# PPU2_And_Connector.net
KiCad netlist of a schematic drawn in Altium Designer
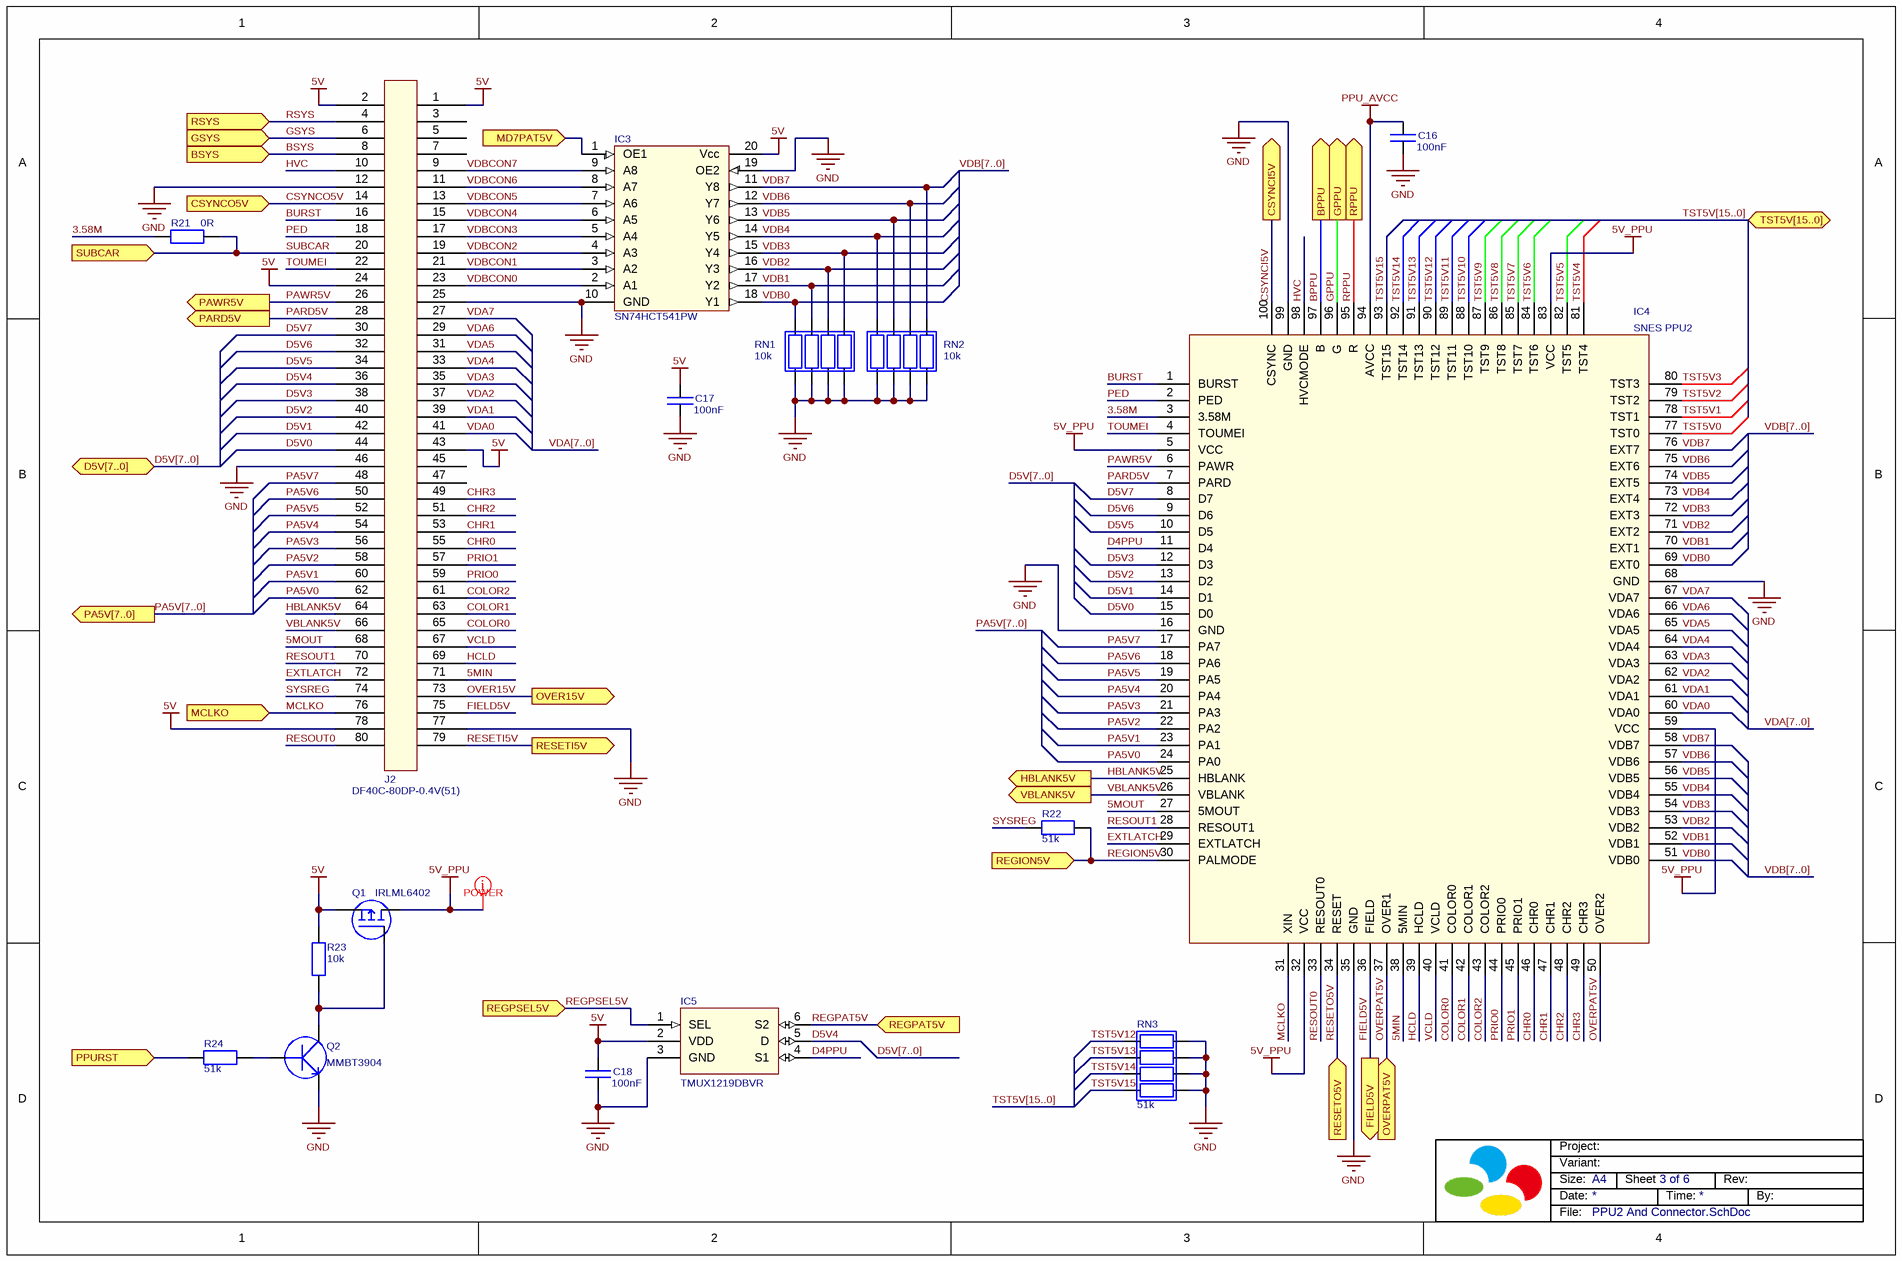
[diagram p0: PPU2 And Connector.SchDoc]

(export (version "E")
  (design (tool "Eeschema 10.0.6"))
  (components
    (comp (ref "C16")
      (value "100nF")
      (footprint "Cap_0402_Chip")
      (fields
        (field (name "TOLERANCE") "±20%")
        (field (name "Comment") "Ceramic Capacitor 100nF 10V ±20% X7R 0402")
      )
      (libsource (lib "PCB") (part "Capacitor"))
    )
    (comp (ref "C17")
      (value "100nF")
      (footprint "Cap_0402_Chip")
      (fields
        (field (name "TOLERANCE") "±20%")
        (field (name "Comment") "Ceramic Capacitor 100nF 10V ±20% X7R 0402")
      )
      (libsource (lib "PCB") (part "Capacitor"))
    )
    (comp (ref "C18")
      (value "100nF")
      (footprint "Cap_0402_Chip")
      (fields
        (field (name "TOLERANCE") "±20%")
        (field (name "Comment") "Ceramic Capacitor 100nF 10V ±20% X7R 0402")
      )
      (libsource (lib "PCB") (part "Capacitor"))
    )
    (comp (ref "IC3")
      (value "SN74HCT541")
      (footprint "TSSOP20 Narrow")
      (fields (field (name "MANUFACTURER_PART_NUMBER") "SN74HCT541PW"))
      (libsource (lib "PCB") (part "SN74HCT541"))
    )
    (comp (ref "IC4")
      (value "SNES PPU2")
      (footprint "PPU100Pin")
      (description "PPU2")
      (libsource (lib "PCB") (part "PPU2100Pin"))
    )
    (comp (ref "IC5")
      (value "TMUX1219")
      (footprint "SOT23-6")
      (description "2:1 MUX")
      (fields (field (name "MANUFACTURER_PART_NUMBER") "TMUX1219DBVR"))
      (libsource (lib "PCB") (part "TMUX1219"))
    )
    (comp (ref "J2")
      (value "DF40C-80DP")
      (footprint "DF40C-80DP")
      (description "80Pole Connector")
      (fields (field (name "MANUFACTURER_PART_NUMBER") "DF40C-80DP-0.4V(51)"))
      (libsource (lib "PCB") (part "Conn 80P"))
    )
    (comp (ref "Q1") (value "IRLML6402") (footprint "SOT23_FET") (libsource (lib "PCB") (part "Mosfet1")))
    (comp (ref "Q2") (value "MMBT3904") (footprint "SOT23_Transistor") (libsource (lib "PCB") (part "T_NPN")))
    (comp (ref "R21")
      (value "0R")
      (footprint "Res_0603_Chip")
      (fields (field (name "TOLERANCE") "±1%") (field (name "Comment") "Resistor 0R 0603 ±1%"))
      (libsource (lib "") (part "R_2"))
    )
    (comp (ref "R22")
      (value "51k")
      (footprint "Res_0402_Chip")
      (fields (field (name "TOLERANCE") "±1%") (field (name "Comment") "Resistor 51k 0402 ±1%"))
      (libsource (lib "") (part "R_2"))
    )
    (comp (ref "R23")
      (value "10k")
      (footprint "Res_0402_Chip")
      (fields (field (name "TOLERANCE") "±1%") (field (name "Comment") "Resistor 10k 0402 ±1%"))
      (libsource (lib "") (part "R_1"))
    )
    (comp (ref "R24")
      (value "51k")
      (footprint "Res_0402_Chip")
      (fields (field (name "TOLERANCE") "±1%") (field (name "Comment") "Resistor 51k 0402 ±1%"))
      (libsource (lib "PCB") (part "R"))
    )
    (comp (ref "RN1")
      (value "10k")
      (footprint "1206_Array_Chip")
      (fields (field (name "TOLERANCE") "±1%") (field (name "Comment") "Resistor Network 10k 1206 ±1%"))
      (libsource (lib "") (part "RNetwork_1"))
    )
    (comp (ref "RN2")
      (value "10k")
      (footprint "1206_Array_Chip")
      (fields (field (name "TOLERANCE") "±1%") (field (name "Comment") "Resistor Network 10k 1206 ±1%"))
      (libsource (lib "") (part "RNetwork_1"))
    )
    (comp (ref "RN3")
      (value "51k")
      (footprint "1206_Array_Chip")
      (fields (field (name "TOLERANCE") "±1%") (field (name "Comment") "Resistor Network 51k 1206 ±1%"))
      (libsource (lib "PCB") (part "RNetwork"))
    )
  )
  (nets
    (net (code "1") (name "/3.58M") (class "Default")
      (node (ref "IC4") (pin "3") (pinfunction "3.58M_3") (pintype "passive"))
      (node (ref "R21") (pin "2") (pintype "passive"))
    )
    (net (code "2") (name "/5MIN") (class "Default")
      (node (ref "IC4") (pin "38") (pinfunction "5MIN_38") (pintype "passive"))
      (node (ref "J2") (pin "71") (pintype "passive"))
    )
    (net (code "3") (name "/5MOUT") (class "Default")
      (node (ref "IC4") (pin "27") (pinfunction "5MOUT_27") (pintype "passive"))
      (node (ref "J2") (pin "68") (pintype "passive"))
    )
    (net (code "4") (name "/BPPU") (class "Default")
      (node (ref "IC4") (pin "97") (pinfunction "B_97") (pintype "passive"))
    )
    (net (code "5") (name "/BSYS") (class "Default") (node (ref "J2") (pin "8") (pintype "passive")))
    (net (code "6") (name "/BURST") (class "Default")
      (node (ref "IC4") (pin "1") (pinfunction "BURST_1") (pintype "passive"))
      (node (ref "J2") (pin "16") (pintype "passive"))
    )
    (net (code "7") (name "/CHR0") (class "Default")
      (node (ref "IC4") (pin "46") (pinfunction "CHR0_46") (pintype "passive"))
      (node (ref "J2") (pin "55") (pintype "passive"))
    )
    (net (code "8") (name "/CHR1") (class "Default")
      (node (ref "IC4") (pin "47") (pinfunction "CHR1_47") (pintype "passive"))
      (node (ref "J2") (pin "53") (pintype "passive"))
    )
    (net (code "9") (name "/CHR2") (class "Default")
      (node (ref "IC4") (pin "48") (pinfunction "CHR2_48") (pintype "passive"))
      (node (ref "J2") (pin "51") (pintype "passive"))
    )
    (net (code "10") (name "/CHR3") (class "Default")
      (node (ref "IC4") (pin "49") (pinfunction "CHR3_49") (pintype "passive"))
      (node (ref "J2") (pin "49") (pintype "passive"))
    )
    (net (code "11") (name "/COLOR0") (class "Default")
      (node (ref "IC4") (pin "41") (pinfunction "COLOR0_41") (pintype "passive"))
      (node (ref "J2") (pin "65") (pintype "passive"))
    )
    (net (code "12") (name "/COLOR1") (class "Default")
      (node (ref "IC4") (pin "42") (pinfunction "COLOR1_42") (pintype "passive"))
      (node (ref "J2") (pin "63") (pintype "passive"))
    )
    (net (code "13") (name "/COLOR2") (class "Default")
      (node (ref "IC4") (pin "43") (pinfunction "COLOR2_43") (pintype "passive"))
      (node (ref "J2") (pin "61") (pintype "passive"))
    )
    (net (code "14") (name "/CSYNCI5V") (class "Default")
      (node (ref "IC4") (pin "100") (pinfunction "CSYNC_100") (pintype "passive"))
    )
    (net (code "15") (name "/CSYNCO5V") (class "Default") (node (ref "J2") (pin "14") (pintype "passive")))
    (net (code "16") (name "/D4PPU") (class "Default")
      (node (ref "IC4") (pin "11") (pinfunction "D4_11") (pintype "passive"))
      (node (ref "IC5") (pin "4") (pinfunction "S1_4") (pintype "bidirectional"))
    )
    (net (code "17") (name "/D5V0") (class "Default")
      (node (ref "IC4") (pin "15") (pinfunction "D0_15") (pintype "passive"))
      (node (ref "J2") (pin "44") (pintype "passive"))
    )
    (net (code "18") (name "/D5V1") (class "Default")
      (node (ref "IC4") (pin "14") (pinfunction "D1_14") (pintype "passive"))
      (node (ref "J2") (pin "42") (pintype "passive"))
    )
    (net (code "19") (name "/D5V2") (class "Default")
      (node (ref "IC4") (pin "13") (pinfunction "D2_13") (pintype "passive"))
      (node (ref "J2") (pin "40") (pintype "passive"))
    )
    (net (code "20") (name "/D5V3") (class "Default")
      (node (ref "IC4") (pin "12") (pinfunction "D3_12") (pintype "passive"))
      (node (ref "J2") (pin "38") (pintype "passive"))
    )
    (net (code "21") (name "/D5V4") (class "Default")
      (node (ref "IC5") (pin "5") (pinfunction "D_5") (pintype "bidirectional"))
      (node (ref "J2") (pin "36") (pintype "passive"))
    )
    (net (code "22") (name "/D5V5") (class "Default")
      (node (ref "IC4") (pin "10") (pinfunction "D5_10") (pintype "passive"))
      (node (ref "J2") (pin "34") (pintype "passive"))
    )
    (net (code "23") (name "/D5V6") (class "Default")
      (node (ref "IC4") (pin "9") (pinfunction "D6_9") (pintype "passive"))
      (node (ref "J2") (pin "32") (pintype "passive"))
    )
    (net (code "24") (name "/D5V7") (class "Default")
      (node (ref "IC4") (pin "8") (pinfunction "D7_8") (pintype "passive"))
      (node (ref "J2") (pin "30") (pintype "passive"))
    )
    (net (code "26") (name "/EXTLATCH") (class "Default")
      (node (ref "IC4") (pin "29") (pinfunction "EXTLATCH_29") (pintype "passive"))
      (node (ref "J2") (pin "72") (pintype "passive"))
    )
    (net (code "27") (name "/FIELD5V") (class "Default")
      (node (ref "IC4") (pin "36") (pinfunction "FIELD_36") (pintype "passive"))
      (node (ref "J2") (pin "75") (pintype "passive"))
    )
    (net (code "28") (name "/GPPU") (class "Default")
      (node (ref "IC4") (pin "96") (pinfunction "G_96") (pintype "passive"))
    )
    (net (code "29") (name "/GSYS") (class "Default") (node (ref "J2") (pin "6") (pintype "passive")))
    (net (code "30") (name "/HBLANK5V") (class "Default")
      (node (ref "IC4") (pin "25") (pinfunction "HBLANK_25") (pintype "passive"))
      (node (ref "J2") (pin "64") (pintype "passive"))
    )
    (net (code "31") (name "/HCLD") (class "Default")
      (node (ref "IC4") (pin "39") (pinfunction "HCLD_39") (pintype "passive"))
      (node (ref "J2") (pin "69") (pintype "passive"))
    )
    (net (code "32") (name "/HVC") (class "Default")
      (node (ref "IC4") (pin "98") (pinfunction "HVCMODE_98") (pintype "passive"))
      (node (ref "J2") (pin "10") (pintype "passive"))
    )
    (net (code "33") (name "/MCLKO") (class "Default")
      (node (ref "IC4") (pin "31") (pinfunction "XIN_31") (pintype "passive"))
      (node (ref "J2") (pin "76") (pintype "passive"))
    )
    (net (code "34") (name "/MD7PAT5V") (class "Default")
      (node (ref "IC3") (pin "1") (pinfunction "OE1_1") (pintype "input"))
    )
    (net (code "35") (name "/OVER15V") (class "Default") (node (ref "J2") (pin "73") (pintype "passive")))
    (net (code "36") (name "/OVERPAT5V") (class "Default")
      (node (ref "IC4") (pin "37") (pinfunction "OVER1_37") (pintype "passive"))
      (node (ref "IC4") (pin "50") (pinfunction "OVER2_50") (pintype "passive"))
    )
    (net (code "37") (name "/PA5V0") (class "Default")
      (node (ref "IC4") (pin "24") (pinfunction "PA0_24") (pintype "passive"))
      (node (ref "J2") (pin "62") (pintype "passive"))
    )
    (net (code "38") (name "/PA5V1") (class "Default")
      (node (ref "IC4") (pin "23") (pinfunction "PA1_23") (pintype "passive"))
      (node (ref "J2") (pin "60") (pintype "passive"))
    )
    (net (code "39") (name "/PA5V2") (class "Default")
      (node (ref "IC4") (pin "22") (pinfunction "PA2_22") (pintype "passive"))
      (node (ref "J2") (pin "58") (pintype "passive"))
    )
    (net (code "40") (name "/PA5V3") (class "Default")
      (node (ref "IC4") (pin "21") (pinfunction "PA3_21") (pintype "passive"))
      (node (ref "J2") (pin "56") (pintype "passive"))
    )
    (net (code "41") (name "/PA5V4") (class "Default")
      (node (ref "IC4") (pin "20") (pinfunction "PA4_20") (pintype "passive"))
      (node (ref "J2") (pin "54") (pintype "passive"))
    )
    (net (code "42") (name "/PA5V5") (class "Default")
      (node (ref "IC4") (pin "19") (pinfunction "PA5_19") (pintype "passive"))
      (node (ref "J2") (pin "52") (pintype "passive"))
    )
    (net (code "43") (name "/PA5V6") (class "Default")
      (node (ref "IC4") (pin "18") (pinfunction "PA6_18") (pintype "passive"))
      (node (ref "J2") (pin "50") (pintype "passive"))
    )
    (net (code "44") (name "/PA5V7") (class "Default")
      (node (ref "IC4") (pin "17") (pinfunction "PA7_17") (pintype "passive"))
      (node (ref "J2") (pin "48") (pintype "passive"))
    )
    (net (code "46") (name "/PARD5V") (class "Default")
      (node (ref "IC4") (pin "7") (pinfunction "PARD_7") (pintype "passive"))
      (node (ref "J2") (pin "28") (pintype "passive"))
    )
    (net (code "47") (name "/PAWR5V") (class "Default")
      (node (ref "IC4") (pin "6") (pinfunction "PAWR_6") (pintype "passive"))
      (node (ref "J2") (pin "26") (pintype "passive"))
    )
    (net (code "48") (name "/PED") (class "Default")
      (node (ref "IC4") (pin "2") (pinfunction "PED_2") (pintype "passive"))
      (node (ref "J2") (pin "18") (pintype "passive"))
    )
    (net (code "49") (name "/PPURST") (class "Default") (node (ref "R24") (pin "1") (pintype "passive")))
    (net (code "50") (name "/PRIO0") (class "Default")
      (node (ref "IC4") (pin "44") (pinfunction "PRIO0_44") (pintype "passive"))
      (node (ref "J2") (pin "59") (pintype "passive"))
    )
    (net (code "51") (name "/PRIO1") (class "Default")
      (node (ref "IC4") (pin "45") (pinfunction "PRIO1_45") (pintype "passive"))
      (node (ref "J2") (pin "57") (pintype "passive"))
    )
    (net (code "52") (name "/REGION5V") (class "Default")
      (node (ref "IC4") (pin "30") (pinfunction "PALMODE_30") (pintype "passive"))
      (node (ref "R22") (pin "1") (pintype "passive"))
    )
    (net (code "53") (name "/REGPAT5V") (class "Default")
      (node (ref "IC5") (pin "6") (pinfunction "S2_6") (pintype "bidirectional"))
    )
    (net (code "54") (name "/REGPSEL5V") (class "Default")
      (node (ref "IC5") (pin "1") (pinfunction "SEL_1") (pintype "input"))
    )
    (net (code "55") (name "/RESETI5V") (class "Default") (node (ref "J2") (pin "79") (pintype "passive")))
    (net (code "56") (name "/RESETO5V") (class "Default")
      (node (ref "IC4") (pin "34") (pinfunction "RESET_34") (pintype "passive"))
    )
    (net (code "57") (name "/RESOUT0") (class "Default")
      (node (ref "IC4") (pin "33") (pinfunction "RESOUT0_33") (pintype "passive"))
      (node (ref "J2") (pin "80") (pintype "passive"))
    )
    (net (code "58") (name "/RESOUT1") (class "Default")
      (node (ref "IC4") (pin "28") (pinfunction "RESOUT1_28") (pintype "passive"))
      (node (ref "J2") (pin "70") (pintype "passive"))
    )
    (net (code "59") (name "/RPPU") (class "Default")
      (node (ref "IC4") (pin "95") (pinfunction "R_95") (pintype "passive"))
    )
    (net (code "60") (name "/RSYS") (class "Default") (node (ref "J2") (pin "4") (pintype "passive")))
    (net (code "61") (name "/SUBCAR") (class "Default")
      (node (ref "J2") (pin "20") (pintype "passive"))
      (node (ref "R21") (pin "1") (pintype "passive"))
    )
    (net (code "62") (name "/SYSREG") (class "Default")
      (node (ref "J2") (pin "74") (pintype "passive"))
      (node (ref "R22") (pin "2") (pintype "passive"))
    )
    (net (code "63") (name "/TOUMEI") (class "Default")
      (node (ref "IC4") (pin "4") (pinfunction "TOUMEI_4") (pintype "passive"))
      (node (ref "J2") (pin "22") (pintype "passive"))
    )
    (net (code "64") (name "/TST5V0") (class "Default")
      (node (ref "IC4") (pin "77") (pinfunction "TST0_77") (pintype "passive"))
    )
    (net (code "65") (name "/TST5V1") (class "Default")
      (node (ref "IC4") (pin "78") (pinfunction "TST1_78") (pintype "passive"))
    )
    (net (code "66") (name "/TST5V2") (class "Default")
      (node (ref "IC4") (pin "79") (pinfunction "TST2_79") (pintype "passive"))
    )
    (net (code "67") (name "/TST5V3") (class "Default")
      (node (ref "IC4") (pin "80") (pinfunction "TST3_80") (pintype "passive"))
    )
    (net (code "68") (name "/TST5V4") (class "Default")
      (node (ref "IC4") (pin "81") (pinfunction "TST4_81") (pintype "passive"))
    )
    (net (code "69") (name "/TST5V5") (class "Default")
      (node (ref "IC4") (pin "82") (pinfunction "TST5_82") (pintype "passive"))
    )
    (net (code "70") (name "/TST5V6") (class "Default")
      (node (ref "IC4") (pin "84") (pinfunction "TST6_84") (pintype "passive"))
    )
    (net (code "71") (name "/TST5V7") (class "Default")
      (node (ref "IC4") (pin "85") (pinfunction "TST7_85") (pintype "passive"))
    )
    (net (code "72") (name "/TST5V8") (class "Default")
      (node (ref "IC4") (pin "86") (pinfunction "TST8_86") (pintype "passive"))
    )
    (net (code "73") (name "/TST5V9") (class "Default")
      (node (ref "IC4") (pin "87") (pinfunction "TST9_87") (pintype "passive"))
    )
    (net (code "74") (name "/TST5V10") (class "Default")
      (node (ref "IC4") (pin "88") (pinfunction "TST10_88") (pintype "passive"))
    )
    (net (code "75") (name "/TST5V11") (class "Default")
      (node (ref "IC4") (pin "89") (pinfunction "TST11_89") (pintype "passive"))
    )
    (net (code "76") (name "/TST5V12") (class "Default")
      (node (ref "IC4") (pin "90") (pinfunction "TST12_90") (pintype "passive"))
      (node (ref "RN3") (pin "5") (pintype "passive"))
    )
    (net (code "77") (name "/TST5V13") (class "Default")
      (node (ref "IC4") (pin "91") (pinfunction "TST13_91") (pintype "passive"))
      (node (ref "RN3") (pin "6") (pintype "passive"))
    )
    (net (code "78") (name "/TST5V14") (class "Default")
      (node (ref "IC4") (pin "92") (pinfunction "TST14_92") (pintype "passive"))
      (node (ref "RN3") (pin "7") (pintype "passive"))
    )
    (net (code "79") (name "/TST5V15") (class "Default")
      (node (ref "IC4") (pin "93") (pinfunction "TST15_93") (pintype "passive"))
      (node (ref "RN3") (pin "8") (pintype "passive"))
    )
    (net (code "81") (name "/VBLANK5V") (class "Default")
      (node (ref "IC4") (pin "26") (pinfunction "VBLANK_26") (pintype "passive"))
      (node (ref "J2") (pin "66") (pintype "passive"))
    )
    (net (code "82") (name "/VCLD") (class "Default")
      (node (ref "IC4") (pin "40") (pinfunction "VCLD_40") (pintype "passive"))
      (node (ref "J2") (pin "67") (pintype "passive"))
    )
    (net (code "83") (name "/VDA0") (class "Default")
      (node (ref "IC4") (pin "60") (pinfunction "VDA0_60") (pintype "passive"))
      (node (ref "J2") (pin "41") (pintype "passive"))
    )
    (net (code "84") (name "/VDA1") (class "Default")
      (node (ref "IC4") (pin "61") (pinfunction "VDA1_61") (pintype "passive"))
      (node (ref "J2") (pin "39") (pintype "passive"))
    )
    (net (code "85") (name "/VDA2") (class "Default")
      (node (ref "IC4") (pin "62") (pinfunction "VDA2_62") (pintype "passive"))
      (node (ref "J2") (pin "37") (pintype "passive"))
    )
    (net (code "86") (name "/VDA3") (class "Default")
      (node (ref "IC4") (pin "63") (pinfunction "VDA3_63") (pintype "passive"))
      (node (ref "J2") (pin "35") (pintype "passive"))
    )
    (net (code "87") (name "/VDA4") (class "Default")
      (node (ref "IC4") (pin "64") (pinfunction "VDA4_64") (pintype "passive"))
      (node (ref "J2") (pin "33") (pintype "passive"))
    )
    (net (code "88") (name "/VDA5") (class "Default")
      (node (ref "IC4") (pin "65") (pinfunction "VDA5_65") (pintype "passive"))
      (node (ref "J2") (pin "31") (pintype "passive"))
    )
    (net (code "89") (name "/VDA6") (class "Default")
      (node (ref "IC4") (pin "66") (pinfunction "VDA6_66") (pintype "passive"))
      (node (ref "J2") (pin "29") (pintype "passive"))
    )
    (net (code "90") (name "/VDA7") (class "Default")
      (node (ref "IC4") (pin "67") (pinfunction "VDA7_67") (pintype "passive"))
      (node (ref "J2") (pin "27") (pintype "passive"))
    )
    (net (code "92") (name "/VDB0") (class "Default")
      (node (ref "IC3") (pin "18") (pinfunction "Y1_18") (pintype "output"))
      (node (ref "IC4") (pin "51") (pinfunction "VDB0_51") (pintype "passive"))
      (node (ref "IC4") (pin "69") (pinfunction "EXT0_69") (pintype "passive"))
      (node (ref "RN1") (pin "8") (pintype "passive"))
    )
    (net (code "93") (name "/VDB1") (class "Default")
      (node (ref "IC3") (pin "17") (pinfunction "Y2_17") (pintype "output"))
      (node (ref "IC4") (pin "52") (pinfunction "VDB1_52") (pintype "passive"))
      (node (ref "IC4") (pin "70") (pinfunction "EXT1_70") (pintype "passive"))
      (node (ref "RN1") (pin "7") (pintype "passive"))
    )
    (net (code "94") (name "/VDB2") (class "Default")
      (node (ref "IC3") (pin "16") (pinfunction "Y3_16") (pintype "output"))
      (node (ref "IC4") (pin "53") (pinfunction "VDB2_53") (pintype "passive"))
      (node (ref "IC4") (pin "71") (pinfunction "EXT2_71") (pintype "passive"))
      (node (ref "RN1") (pin "6") (pintype "passive"))
    )
    (net (code "95") (name "/VDB3") (class "Default")
      (node (ref "IC3") (pin "15") (pinfunction "Y4_15") (pintype "output"))
      (node (ref "IC4") (pin "54") (pinfunction "VDB3_54") (pintype "passive"))
      (node (ref "IC4") (pin "72") (pinfunction "EXT3_72") (pintype "passive"))
      (node (ref "RN1") (pin "5") (pintype "passive"))
    )
    (net (code "96") (name "/VDB4") (class "Default")
      (node (ref "IC3") (pin "14") (pinfunction "Y5_14") (pintype "output"))
      (node (ref "IC4") (pin "55") (pinfunction "VDB4_55") (pintype "passive"))
      (node (ref "IC4") (pin "73") (pinfunction "EXT4_73") (pintype "passive"))
      (node (ref "RN2") (pin "8") (pintype "passive"))
    )
    (net (code "97") (name "/VDB5") (class "Default")
      (node (ref "IC3") (pin "13") (pinfunction "Y6_13") (pintype "output"))
      (node (ref "IC4") (pin "56") (pinfunction "VDB5_56") (pintype "passive"))
      (node (ref "IC4") (pin "74") (pinfunction "EXT5_74") (pintype "passive"))
      (node (ref "RN2") (pin "7") (pintype "passive"))
    )
    (net (code "98") (name "/VDB6") (class "Default")
      (node (ref "IC3") (pin "12") (pinfunction "Y7_12") (pintype "output"))
      (node (ref "IC4") (pin "57") (pinfunction "VDB6_57") (pintype "passive"))
      (node (ref "IC4") (pin "75") (pinfunction "EXT6_75") (pintype "passive"))
      (node (ref "RN2") (pin "6") (pintype "passive"))
    )
    (net (code "99") (name "/VDB7") (class "Default")
      (node (ref "IC3") (pin "11") (pinfunction "Y8_11") (pintype "output"))
      (node (ref "IC4") (pin "58") (pinfunction "VDB7_58") (pintype "passive"))
      (node (ref "IC4") (pin "76") (pinfunction "EXT7_76") (pintype "passive"))
      (node (ref "RN2") (pin "5") (pintype "passive"))
    )
    (net (code "100") (name "/VDBCON0") (class "Default")
      (node (ref "IC3") (pin "2") (pinfunction "A1_2") (pintype "input"))
      (node (ref "J2") (pin "23") (pintype "passive"))
    )
    (net (code "101") (name "/VDBCON1") (class "Default")
      (node (ref "IC3") (pin "3") (pinfunction "A2_3") (pintype "input"))
      (node (ref "J2") (pin "21") (pintype "passive"))
    )
    (net (code "102") (name "/VDBCON2") (class "Default")
      (node (ref "IC3") (pin "4") (pinfunction "A3_4") (pintype "input"))
      (node (ref "J2") (pin "19") (pintype "passive"))
    )
    (net (code "103") (name "/VDBCON3") (class "Default")
      (node (ref "IC3") (pin "5") (pinfunction "A4_5") (pintype "input"))
      (node (ref "J2") (pin "17") (pintype "passive"))
    )
    (net (code "104") (name "/VDBCON4") (class "Default")
      (node (ref "IC3") (pin "6") (pinfunction "A5_6") (pintype "input"))
      (node (ref "J2") (pin "15") (pintype "passive"))
    )
    (net (code "105") (name "/VDBCON5") (class "Default")
      (node (ref "IC3") (pin "7") (pinfunction "A6_7") (pintype "input"))
      (node (ref "J2") (pin "13") (pintype "passive"))
    )
    (net (code "106") (name "/VDBCON6") (class "Default")
      (node (ref "IC3") (pin "8") (pinfunction "A7_8") (pintype "input"))
      (node (ref "J2") (pin "11") (pintype "passive"))
    )
    (net (code "107") (name "/VDBCON7") (class "Default")
      (node (ref "IC3") (pin "9") (pinfunction "A8_9") (pintype "input"))
      (node (ref "J2") (pin "9") (pintype "passive"))
    )
    (net (code "109") (name "5V") (class "Default")
      (node (ref "C17") (pin "1") (pintype "passive"))
      (node (ref "C18") (pin "1") (pintype "passive"))
      (node (ref "IC3") (pin "20") (pinfunction "Vcc_20") (pintype "power_in"))
      (node (ref "IC5") (pin "2") (pinfunction "VDD_2") (pintype "power_in"))
      (node (ref "J2") (pin "1") (pintype "passive"))
      (node (ref "J2") (pin "2") (pintype "passive"))
      (node (ref "J2") (pin "24") (pintype "passive"))
      (node (ref "J2") (pin "43") (pintype "passive"))
      (node (ref "J2") (pin "78") (pintype "passive"))
      (node (ref "Q1") (pin "S") (pinfunction "S_S") (pintype "passive"))
      (node (ref "R23") (pin "1") (pintype "passive"))
    )
    (net (code "110") (name "5V_PPU") (class "Default")
      (node (ref "IC4") (pin "32") (pinfunction "VCC_32") (pintype "passive"))
      (node (ref "IC4") (pin "5") (pinfunction "VCC_5") (pintype "passive"))
      (node (ref "IC4") (pin "59") (pinfunction "VCC_59") (pintype "passive"))
      (node (ref "IC4") (pin "83") (pinfunction "VCC_83") (pintype "passive"))
      (node (ref "Q1") (pin "D") (pinfunction "D_D") (pintype "passive"))
    )
    (net (code "111") (name "GND") (class "Default")
      (node (ref "C16") (pin "2") (pintype "passive"))
      (node (ref "C17") (pin "2") (pintype "passive"))
      (node (ref "C18") (pin "2") (pintype "passive"))
      (node (ref "IC3") (pin "10") (pinfunction "GND_10") (pintype "power_in"))
      (node (ref "IC3") (pin "19") (pinfunction "OE2_19") (pintype "input"))
      (node (ref "IC4") (pin "16") (pinfunction "GND_16") (pintype "passive"))
      (node (ref "IC4") (pin "35") (pinfunction "GND_35") (pintype "passive"))
      (node (ref "IC4") (pin "68") (pinfunction "GND_68") (pintype "passive"))
      (node (ref "IC4") (pin "99") (pinfunction "GND_99") (pintype "passive"))
      (node (ref "IC5") (pin "3") (pinfunction "GND_3") (pintype "power_in"))
      (node (ref "J2") (pin "12") (pintype "passive"))
      (node (ref "J2") (pin "25") (pintype "passive"))
      (node (ref "J2") (pin "46") (pintype "passive"))
      (node (ref "J2") (pin "77") (pintype "passive"))
      (node (ref "Q2") (pin "E") (pinfunction "E_E") (pintype "passive"))
      (node (ref "RN1") (pin "1") (pintype "passive"))
      (node (ref "RN1") (pin "2") (pintype "passive"))
      (node (ref "RN1") (pin "3") (pintype "passive"))
      (node (ref "RN1") (pin "4") (pintype "passive"))
      (node (ref "RN2") (pin "1") (pintype "passive"))
      (node (ref "RN2") (pin "2") (pintype "passive"))
      (node (ref "RN2") (pin "3") (pintype "passive"))
      (node (ref "RN2") (pin "4") (pintype "passive"))
      (node (ref "RN3") (pin "1") (pintype "passive"))
      (node (ref "RN3") (pin "2") (pintype "passive"))
      (node (ref "RN3") (pin "3") (pintype "passive"))
      (node (ref "RN3") (pin "4") (pintype "passive"))
    )
    (net (code "112") (name "Net-(Q1-PadG)") (class "Default")
      (node (ref "Q1") (pin "G") (pinfunction "G_G") (pintype "passive"))
      (node (ref "Q2") (pin "C") (pinfunction "C_C") (pintype "passive"))
      (node (ref "R23") (pin "2") (pintype "passive"))
    )
    (net (code "113") (name "Net-(Q2-PadB)") (class "Default")
      (node (ref "Q2") (pin "B") (pinfunction "B_B") (pintype "passive"))
      (node (ref "R24") (pin "2") (pintype "passive"))
    )
    (net (code "114") (name "PPU_AVCC") (class "Default")
      (node (ref "C16") (pin "1") (pintype "passive"))
      (node (ref "IC4") (pin "94") (pinfunction "AVCC_94") (pintype "passive"))
    )
    (net (code "115") (name "unconnected-(J2-Pad3)") (class "Default")
      (node (ref "J2") (pin "3") (pintype "passive"))
    )
    (net (code "116") (name "unconnected-(J2-Pad5)") (class "Default")
      (node (ref "J2") (pin "5") (pintype "passive"))
    )
    (net (code "117") (name "unconnected-(J2-Pad7)") (class "Default")
      (node (ref "J2") (pin "7") (pintype "passive"))
    )
    (net (code "118") (name "unconnected-(J2-Pad45)") (class "Default")
      (node (ref "J2") (pin "45") (pintype "passive"))
    )
    (net (code "119") (name "unconnected-(J2-Pad47)") (class "Default")
      (node (ref "J2") (pin "47") (pintype "passive"))
    )
  )
)
